# Sheet3.net
KiCad netlist of a schematic drawn in Altium Designer
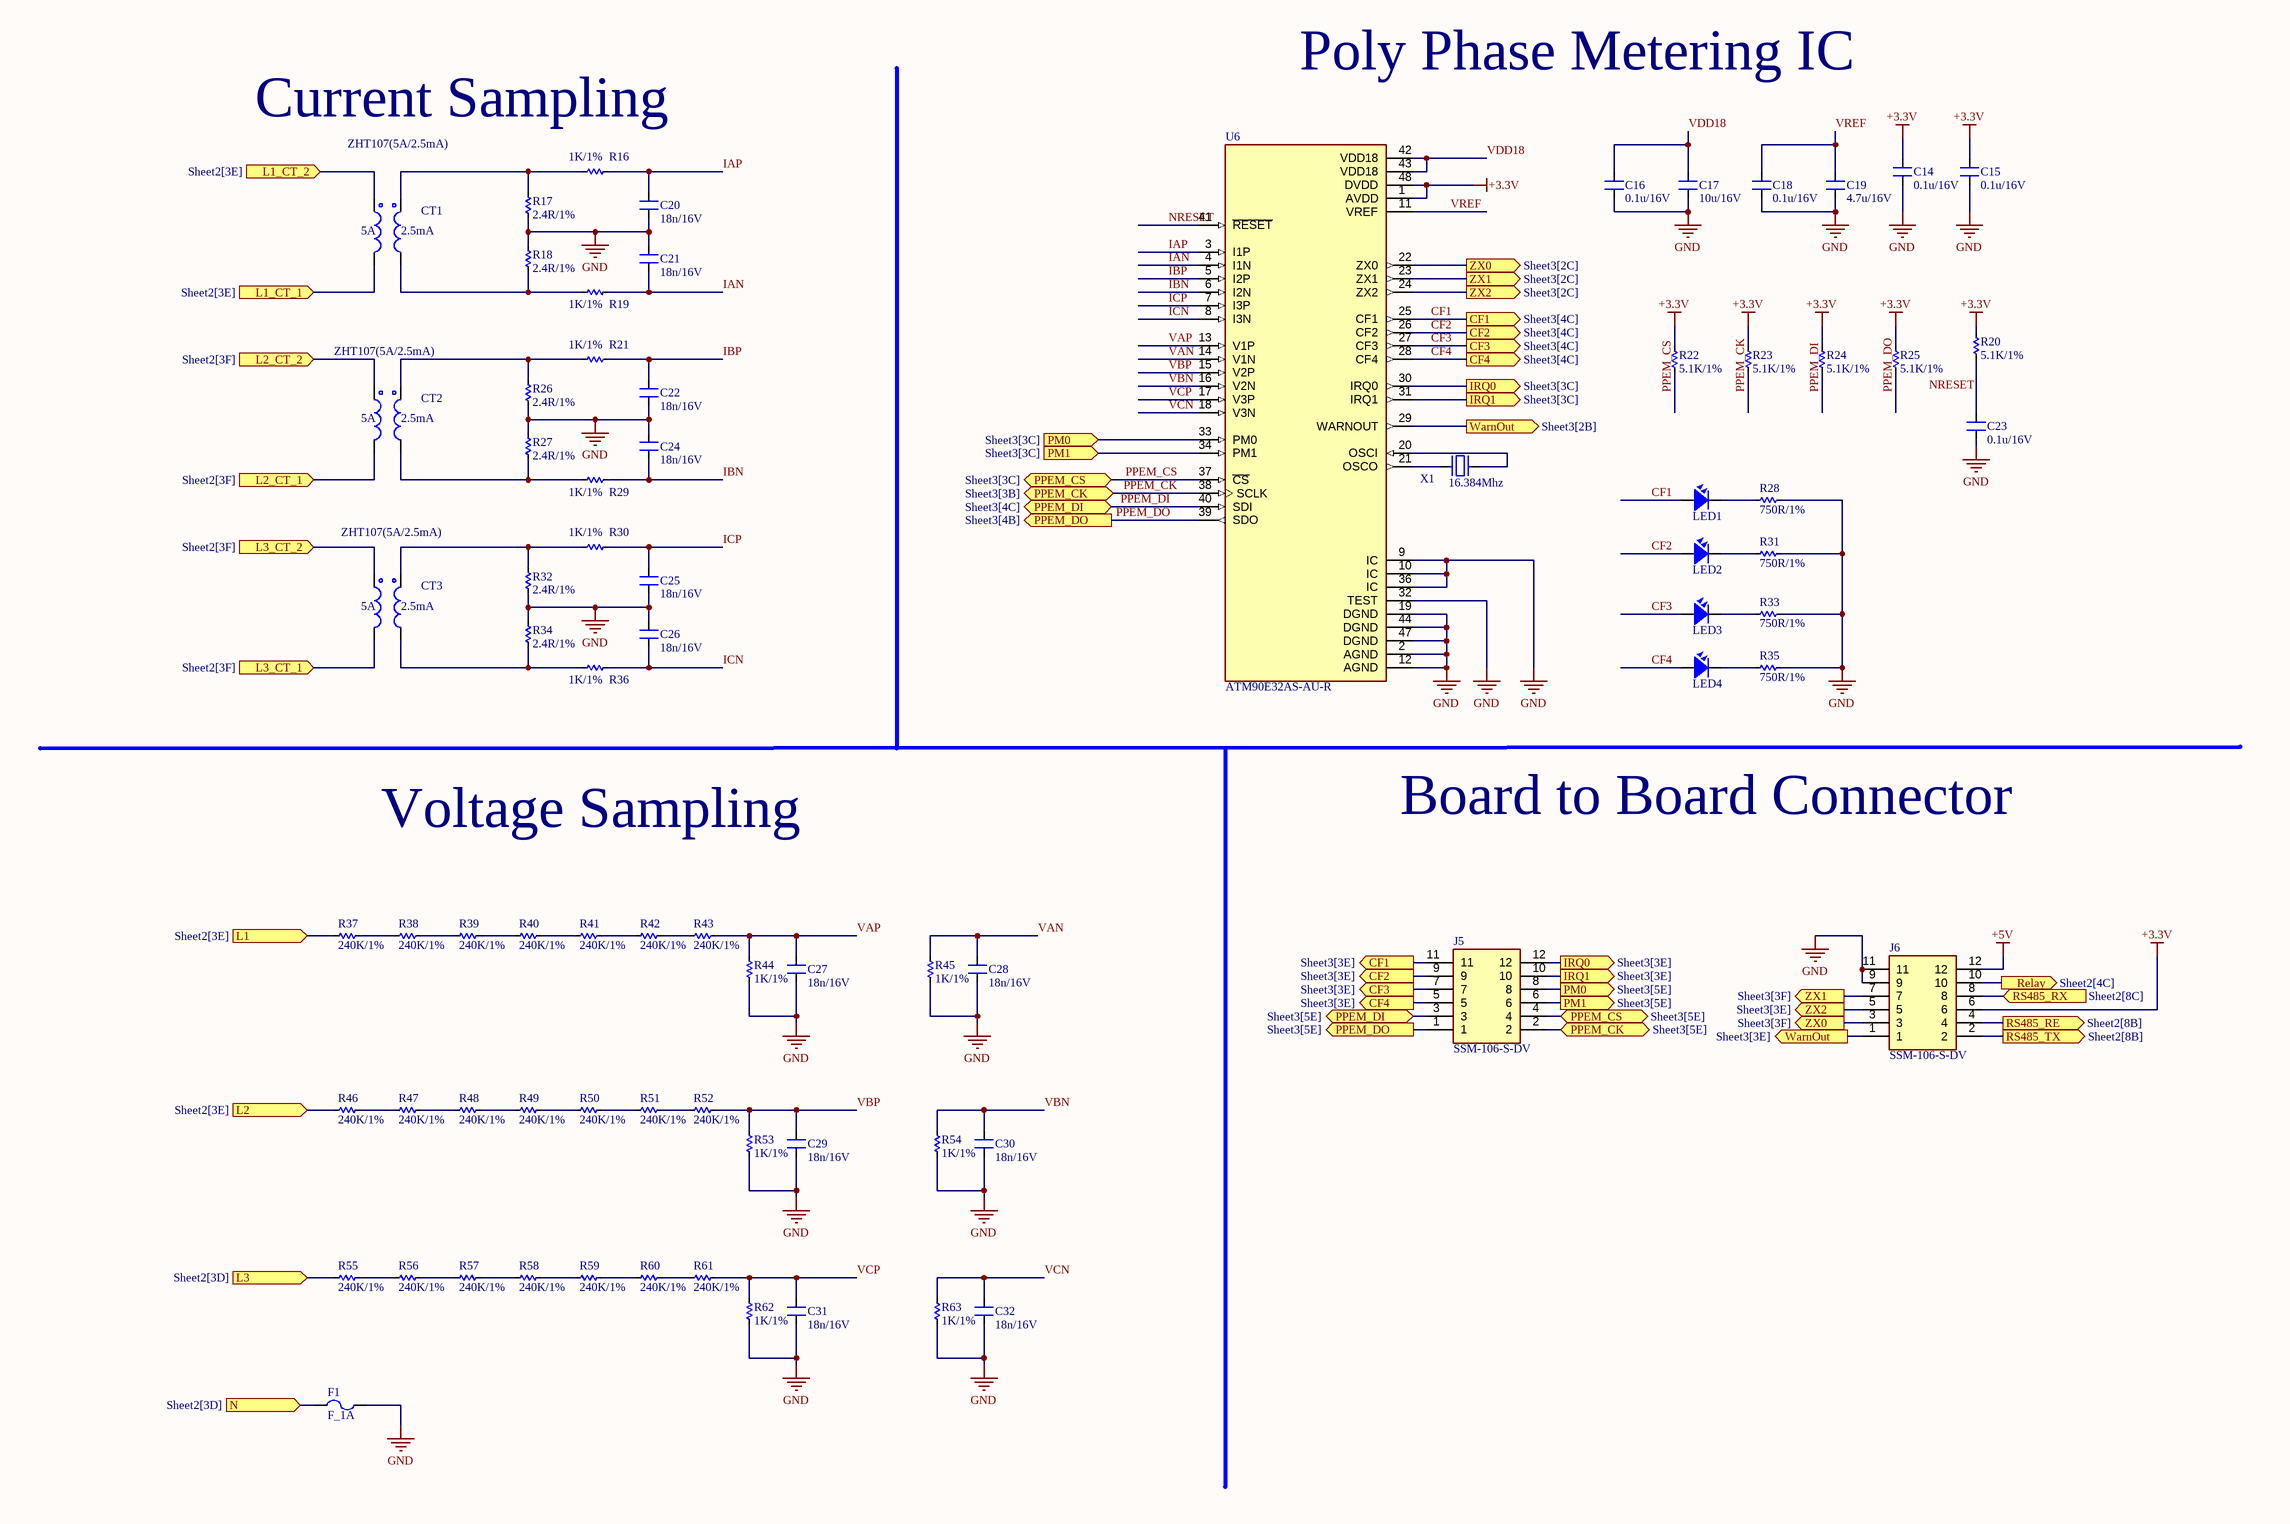
[diagram p0: Sheet3.SchDoc]

(export (version "E")
  (design (tool "Eeschema 10.0.6"))
  (components
    (comp (ref "C14")
      (value "0.1u/16V")
      (footprint "CAP_C_2012X110")
      (libsource (lib "DAK_Altium_Integrated_Lib") (part "CAP_SMD"))
    )
    (comp (ref "C15")
      (value "0.1u/16V")
      (footprint "CAP_C_2012X110")
      (libsource (lib "DAK_Altium_Integrated_Lib") (part "CAP_SMD"))
    )
    (comp (ref "C16")
      (value "0.1u/16V")
      (footprint "CAP_C_2012X110")
      (libsource (lib "DAK_Altium_Integrated_Lib") (part "CAP_SMD"))
    )
    (comp (ref "C17")
      (value "10u/16V")
      (footprint "CAP_C_2012X110")
      (libsource (lib "DAK_Altium_Integrated_Lib") (part "CAP_SMD"))
    )
    (comp (ref "C18")
      (value "0.1u/16V")
      (footprint "CAP_C_2012X110")
      (libsource (lib "DAK_Altium_Integrated_Lib") (part "CAP_SMD"))
    )
    (comp (ref "C19")
      (value "4.7u/16V")
      (footprint "CAP_C_2012X110")
      (libsource (lib "DAK_Altium_Integrated_Lib") (part "CAP_SMD"))
    )
    (comp (ref "C20")
      (value "18n/16V")
      (footprint "CAP_C_2012X110")
      (libsource (lib "DAK_Altium_Integrated_Lib") (part "CAP_SMD"))
    )
    (comp (ref "C21")
      (value "18n/16V")
      (footprint "CAP_C_2012X110")
      (libsource (lib "DAK_Altium_Integrated_Lib") (part "CAP_SMD"))
    )
    (comp (ref "C22")
      (value "18n/16V")
      (footprint "CAP_C_2012X110")
      (libsource (lib "DAK_Altium_Integrated_Lib") (part "CAP_SMD"))
    )
    (comp (ref "C23")
      (value "0.1u/16V")
      (footprint "CAP_C_2012X110")
      (libsource (lib "DAK_Altium_Integrated_Lib") (part "CAP_SMD"))
    )
    (comp (ref "C24")
      (value "18n/16V")
      (footprint "CAP_C_2012X110")
      (libsource (lib "DAK_Altium_Integrated_Lib") (part "CAP_SMD"))
    )
    (comp (ref "C25")
      (value "18n/16V")
      (footprint "CAP_C_2012X110")
      (libsource (lib "DAK_Altium_Integrated_Lib") (part "CAP_SMD"))
    )
    (comp (ref "C26")
      (value "18n/16V")
      (footprint "CAP_C_2012X110")
      (libsource (lib "DAK_Altium_Integrated_Lib") (part "CAP_SMD"))
    )
    (comp (ref "C27")
      (value "18n/16V")
      (footprint "CAP_C_2012X110")
      (libsource (lib "DAK_Altium_Integrated_Lib") (part "CAP_SMD"))
    )
    (comp (ref "C28")
      (value "18n/16V")
      (footprint "CAP_C_2012X110")
      (libsource (lib "DAK_Altium_Integrated_Lib") (part "CAP_SMD"))
    )
    (comp (ref "C29")
      (value "18n/16V")
      (footprint "CAP_C_2012X110")
      (libsource (lib "DAK_Altium_Integrated_Lib") (part "CAP_SMD"))
    )
    (comp (ref "C30")
      (value "18n/16V")
      (footprint "CAP_C_2012X110")
      (libsource (lib "DAK_Altium_Integrated_Lib") (part "CAP_SMD"))
    )
    (comp (ref "C31")
      (value "18n/16V")
      (footprint "CAP_C_2012X110")
      (libsource (lib "DAK_Altium_Integrated_Lib") (part "CAP_SMD"))
    )
    (comp (ref "C32")
      (value "18n/16V")
      (footprint "CAP_C_2012X110")
      (libsource (lib "DAK_Altium_Integrated_Lib") (part "CAP_SMD"))
    )
    (comp (ref "CT1")
      (value "ZHT107(5A/2.5mA)")
      (footprint "ZHT107")
      (description "C5183046")
      (libsource (lib "PowerMeter") (part "ZHT-107"))
    )
    (comp (ref "CT2")
      (value "ZHT107(5A/2.5mA)")
      (footprint "ZHT107")
      (description "C5183046")
      (libsource (lib "PowerMeter") (part "ZHT-107"))
    )
    (comp (ref "CT3")
      (value "ZHT107(5A/2.5mA)")
      (footprint "ZHT107")
      (description "C5183046")
      (libsource (lib "PowerMeter") (part "ZHT-107"))
    )
    (comp (ref "F1")
      (value "F_1A")
      (footprint "FUSC6127X294N")
      (description "Fuse")
      (fields (field (name "DESIGNED BY") "VanDungEvn"))
      (libsource (lib "PowerMeter") (part "Fuse"))
    )
    (comp (ref "J5")
      (value "SSM-106-S-DV")
      (footprint "SSM-106-XXX-DV-BE")
      (description "Connector")
      (fields
        (field (name "MANUFACTURER_PART_NUMBER") "SSM-105-S-DV")
        (field (name "MOUSER PART NUMBER") "200-SSM105SDV")
      )
      (libsource (lib "PowerMeter") (part "SSM-106-S-DV"))
    )
    (comp (ref "J6")
      (value "SSM-106-S-DV")
      (footprint "SSM-106-XXX-DV-BE")
      (description "Connector")
      (fields
        (field (name "MANUFACTURER_PART_NUMBER") "SSM-105-S-DV")
        (field (name "MOUSER PART NUMBER") "200-SSM105SDV")
      )
      (libsource (lib "PowerMeter") (part "SSM-106-S-DV"))
    )
    (comp (ref "LED1") (value "LED") (footprint "LED-0805-Blue") (libsource (lib "Library") (part "LED SMD")))
    (comp (ref "LED2") (value "LED") (footprint "LED-0805-Blue") (libsource (lib "Library") (part "LED SMD")))
    (comp (ref "LED3") (value "LED") (footprint "LED-0805-Blue") (libsource (lib "Library") (part "LED SMD")))
    (comp (ref "LED4") (value "LED") (footprint "LED-0805-Blue") (libsource (lib "Library") (part "LED SMD")))
    (comp (ref "R16")
      (value "1K/1%")
      (footprint "RES_C_2012X65")
      (description "Resistor")
      (fields
        (field (name "MANUFACTURER") "Generic Components")
        (field (name "PUBLISHER") "Altium Hobart Technology Centre")
      )
      (libsource (lib "Library") (part "Res-SMD"))
    )
    (comp (ref "R17")
      (value "2.4R/1%")
      (footprint "RES_C_2012X65")
      (description "Resistor")
      (fields
        (field (name "MANUFACTURER") "Generic Components")
        (field (name "PUBLISHER") "Altium Hobart Technology Centre")
      )
      (libsource (lib "Library") (part "Res-SMD"))
    )
    (comp (ref "R18")
      (value "2.4R/1%")
      (footprint "RES_C_2012X65")
      (description "Resistor")
      (fields
        (field (name "MANUFACTURER") "Generic Components")
        (field (name "PUBLISHER") "Altium Hobart Technology Centre")
      )
      (libsource (lib "Library") (part "Res-SMD"))
    )
    (comp (ref "R19")
      (value "1K/1%")
      (footprint "RES_C_2012X65")
      (description "Resistor")
      (fields
        (field (name "MANUFACTURER") "Generic Components")
        (field (name "PUBLISHER") "Altium Hobart Technology Centre")
      )
      (libsource (lib "Library") (part "Res-SMD"))
    )
    (comp (ref "R20")
      (value "5.1K/1%")
      (footprint "RES_C_2012X65")
      (description "Resistor")
      (fields
        (field (name "MANUFACTURER") "Generic Components")
        (field (name "PUBLISHER") "Altium Hobart Technology Centre")
      )
      (libsource (lib "Library") (part "Res-SMD"))
    )
    (comp (ref "R21")
      (value "1K/1%")
      (footprint "RES_C_2012X65")
      (description "Resistor")
      (fields
        (field (name "MANUFACTURER") "Generic Components")
        (field (name "PUBLISHER") "Altium Hobart Technology Centre")
      )
      (libsource (lib "Library") (part "Res-SMD"))
    )
    (comp (ref "R22")
      (value "5.1K/1%")
      (footprint "RES_C_2012X65")
      (description "Resistor")
      (fields
        (field (name "MANUFACTURER") "Generic Components")
        (field (name "PUBLISHER") "Altium Hobart Technology Centre")
      )
      (libsource (lib "Library") (part "Res-SMD"))
    )
    (comp (ref "R23")
      (value "5.1K/1%")
      (footprint "RES_C_2012X65")
      (description "Resistor")
      (fields
        (field (name "MANUFACTURER") "Generic Components")
        (field (name "PUBLISHER") "Altium Hobart Technology Centre")
      )
      (libsource (lib "Library") (part "Res-SMD"))
    )
    (comp (ref "R24")
      (value "5.1K/1%")
      (footprint "RES_C_2012X65")
      (description "Resistor")
      (fields
        (field (name "MANUFACTURER") "Generic Components")
        (field (name "PUBLISHER") "Altium Hobart Technology Centre")
      )
      (libsource (lib "Library") (part "Res-SMD"))
    )
    (comp (ref "R25")
      (value "5.1K/1%")
      (footprint "RES_C_2012X65")
      (description "Resistor")
      (fields
        (field (name "MANUFACTURER") "Generic Components")
        (field (name "PUBLISHER") "Altium Hobart Technology Centre")
      )
      (libsource (lib "Library") (part "Res-SMD"))
    )
    (comp (ref "R26")
      (value "2.4R/1%")
      (footprint "RES_C_2012X65")
      (description "Resistor")
      (fields
        (field (name "MANUFACTURER") "Generic Components")
        (field (name "PUBLISHER") "Altium Hobart Technology Centre")
      )
      (libsource (lib "Library") (part "Res-SMD"))
    )
    (comp (ref "R27")
      (value "2.4R/1%")
      (footprint "RES_C_2012X65")
      (description "Resistor")
      (fields
        (field (name "MANUFACTURER") "Generic Components")
        (field (name "PUBLISHER") "Altium Hobart Technology Centre")
      )
      (libsource (lib "Library") (part "Res-SMD"))
    )
    (comp (ref "R28")
      (value "750R/1%")
      (footprint "RES_C_2012X65")
      (description "Resistor")
      (fields
        (field (name "MANUFACTURER") "Generic Components")
        (field (name "PUBLISHER") "Altium Hobart Technology Centre")
      )
      (libsource (lib "Library") (part "Res-SMD"))
    )
    (comp (ref "R29")
      (value "1K/1%")
      (footprint "RES_C_2012X65")
      (description "Resistor")
      (fields
        (field (name "MANUFACTURER") "Generic Components")
        (field (name "PUBLISHER") "Altium Hobart Technology Centre")
      )
      (libsource (lib "Library") (part "Res-SMD"))
    )
    (comp (ref "R30")
      (value "1K/1%")
      (footprint "RES_C_2012X65")
      (description "Resistor")
      (fields
        (field (name "MANUFACTURER") "Generic Components")
        (field (name "PUBLISHER") "Altium Hobart Technology Centre")
      )
      (libsource (lib "Library") (part "Res-SMD"))
    )
    (comp (ref "R31")
      (value "750R/1%")
      (footprint "RES_C_2012X65")
      (description "Resistor")
      (fields
        (field (name "MANUFACTURER") "Generic Components")
        (field (name "PUBLISHER") "Altium Hobart Technology Centre")
      )
      (libsource (lib "Library") (part "Res-SMD"))
    )
    (comp (ref "R32")
      (value "2.4R/1%")
      (footprint "RES_C_2012X65")
      (description "Resistor")
      (fields
        (field (name "MANUFACTURER") "Generic Components")
        (field (name "PUBLISHER") "Altium Hobart Technology Centre")
      )
      (libsource (lib "Library") (part "Res-SMD"))
    )
    (comp (ref "R33")
      (value "750R/1%")
      (footprint "RES_C_2012X65")
      (description "Resistor")
      (fields
        (field (name "MANUFACTURER") "Generic Components")
        (field (name "PUBLISHER") "Altium Hobart Technology Centre")
      )
      (libsource (lib "Library") (part "Res-SMD"))
    )
    (comp (ref "R34")
      (value "2.4R/1%")
      (footprint "RES_C_2012X65")
      (description "Resistor")
      (fields
        (field (name "MANUFACTURER") "Generic Components")
        (field (name "PUBLISHER") "Altium Hobart Technology Centre")
      )
      (libsource (lib "Library") (part "Res-SMD"))
    )
    (comp (ref "R35")
      (value "750R/1%")
      (footprint "RES_C_2012X65")
      (description "Resistor")
      (fields
        (field (name "MANUFACTURER") "Generic Components")
        (field (name "PUBLISHER") "Altium Hobart Technology Centre")
      )
      (libsource (lib "Library") (part "Res-SMD"))
    )
    (comp (ref "R36")
      (value "1K/1%")
      (footprint "RES_C_2012X65")
      (description "Resistor")
      (fields
        (field (name "MANUFACTURER") "Generic Components")
        (field (name "PUBLISHER") "Altium Hobart Technology Centre")
      )
      (libsource (lib "Library") (part "Res-SMD"))
    )
    (comp (ref "R37")
      (value "240K/1%")
      (footprint "RES_C_2012X65")
      (description "Resistor")
      (fields
        (field (name "MANUFACTURER") "Generic Components")
        (field (name "PUBLISHER") "Altium Hobart Technology Centre")
      )
      (libsource (lib "Library") (part "Res-SMD"))
    )
    (comp (ref "R38")
      (value "240K/1%")
      (footprint "RES_C_2012X65")
      (description "Resistor")
      (fields
        (field (name "MANUFACTURER") "Generic Components")
        (field (name "PUBLISHER") "Altium Hobart Technology Centre")
      )
      (libsource (lib "Library") (part "Res-SMD"))
    )
    (comp (ref "R39")
      (value "240K/1%")
      (footprint "RES_C_2012X65")
      (description "Resistor")
      (fields
        (field (name "MANUFACTURER") "Generic Components")
        (field (name "PUBLISHER") "Altium Hobart Technology Centre")
      )
      (libsource (lib "Library") (part "Res-SMD"))
    )
    (comp (ref "R40")
      (value "240K/1%")
      (footprint "RES_C_2012X65")
      (description "Resistor")
      (fields
        (field (name "MANUFACTURER") "Generic Components")
        (field (name "PUBLISHER") "Altium Hobart Technology Centre")
      )
      (libsource (lib "Library") (part "Res-SMD"))
    )
    (comp (ref "R41")
      (value "240K/1%")
      (footprint "RES_C_2012X65")
      (description "Resistor")
      (fields
        (field (name "MANUFACTURER") "Generic Components")
        (field (name "PUBLISHER") "Altium Hobart Technology Centre")
      )
      (libsource (lib "Library") (part "Res-SMD"))
    )
    (comp (ref "R42")
      (value "240K/1%")
      (footprint "RES_C_2012X65")
      (description "Resistor")
      (fields
        (field (name "MANUFACTURER") "Generic Components")
        (field (name "PUBLISHER") "Altium Hobart Technology Centre")
      )
      (libsource (lib "Library") (part "Res-SMD"))
    )
    (comp (ref "R43")
      (value "240K/1%")
      (footprint "RES_C_2012X65")
      (description "Resistor")
      (fields
        (field (name "MANUFACTURER") "Generic Components")
        (field (name "PUBLISHER") "Altium Hobart Technology Centre")
      )
      (libsource (lib "Library") (part "Res-SMD"))
    )
    (comp (ref "R44")
      (value "1K/1%")
      (footprint "RES_C_2012X65")
      (description "Resistor")
      (fields
        (field (name "MANUFACTURER") "Generic Components")
        (field (name "PUBLISHER") "Altium Hobart Technology Centre")
      )
      (libsource (lib "Library") (part "Res-SMD"))
    )
    (comp (ref "R45")
      (value "1K/1%")
      (footprint "RES_C_2012X65")
      (description "Resistor")
      (fields
        (field (name "MANUFACTURER") "Generic Components")
        (field (name "PUBLISHER") "Altium Hobart Technology Centre")
      )
      (libsource (lib "Library") (part "Res-SMD"))
    )
    (comp (ref "R46")
      (value "240K/1%")
      (footprint "RES_C_2012X65")
      (description "Resistor")
      (fields
        (field (name "MANUFACTURER") "Generic Components")
        (field (name "PUBLISHER") "Altium Hobart Technology Centre")
      )
      (libsource (lib "Library") (part "Res-SMD"))
    )
    (comp (ref "R47")
      (value "240K/1%")
      (footprint "RES_C_2012X65")
      (description "Resistor")
      (fields
        (field (name "MANUFACTURER") "Generic Components")
        (field (name "PUBLISHER") "Altium Hobart Technology Centre")
      )
      (libsource (lib "Library") (part "Res-SMD"))
    )
    (comp (ref "R48")
      (value "240K/1%")
      (footprint "RES_C_2012X65")
      (description "Resistor")
      (fields
        (field (name "MANUFACTURER") "Generic Components")
        (field (name "PUBLISHER") "Altium Hobart Technology Centre")
      )
      (libsource (lib "Library") (part "Res-SMD"))
    )
    (comp (ref "R49")
      (value "240K/1%")
      (footprint "RES_C_2012X65")
      (description "Resistor")
      (fields
        (field (name "MANUFACTURER") "Generic Components")
        (field (name "PUBLISHER") "Altium Hobart Technology Centre")
      )
      (libsource (lib "Library") (part "Res-SMD"))
    )
    (comp (ref "R50")
      (value "240K/1%")
      (footprint "RES_C_2012X65")
      (description "Resistor")
      (fields
        (field (name "MANUFACTURER") "Generic Components")
        (field (name "PUBLISHER") "Altium Hobart Technology Centre")
      )
      (libsource (lib "Library") (part "Res-SMD"))
    )
    (comp (ref "R51")
      (value "240K/1%")
      (footprint "RES_C_2012X65")
      (description "Resistor")
      (fields
        (field (name "MANUFACTURER") "Generic Components")
        (field (name "PUBLISHER") "Altium Hobart Technology Centre")
      )
      (libsource (lib "Library") (part "Res-SMD"))
    )
    (comp (ref "R52")
      (value "240K/1%")
      (footprint "RES_C_2012X65")
      (description "Resistor")
      (fields
        (field (name "MANUFACTURER") "Generic Components")
        (field (name "PUBLISHER") "Altium Hobart Technology Centre")
      )
      (libsource (lib "Library") (part "Res-SMD"))
    )
    (comp (ref "R53")
      (value "1K/1%")
      (footprint "RES_C_2012X65")
      (description "Resistor")
      (fields
        (field (name "MANUFACTURER") "Generic Components")
        (field (name "PUBLISHER") "Altium Hobart Technology Centre")
      )
      (libsource (lib "Library") (part "Res-SMD"))
    )
    (comp (ref "R54")
      (value "1K/1%")
      (footprint "RES_C_2012X65")
      (description "Resistor")
      (fields
        (field (name "MANUFACTURER") "Generic Components")
        (field (name "PUBLISHER") "Altium Hobart Technology Centre")
      )
      (libsource (lib "Library") (part "Res-SMD"))
    )
    (comp (ref "R55")
      (value "240K/1%")
      (footprint "RES_C_2012X65")
      (description "Resistor")
      (fields
        (field (name "MANUFACTURER") "Generic Components")
        (field (name "PUBLISHER") "Altium Hobart Technology Centre")
      )
      (libsource (lib "Library") (part "Res-SMD"))
    )
    (comp (ref "R56")
      (value "240K/1%")
      (footprint "RES_C_2012X65")
      (description "Resistor")
      (fields
        (field (name "MANUFACTURER") "Generic Components")
        (field (name "PUBLISHER") "Altium Hobart Technology Centre")
      )
      (libsource (lib "Library") (part "Res-SMD"))
    )
    (comp (ref "R57")
      (value "240K/1%")
      (footprint "RES_C_2012X65")
      (description "Resistor")
      (fields
        (field (name "MANUFACTURER") "Generic Components")
        (field (name "PUBLISHER") "Altium Hobart Technology Centre")
      )
      (libsource (lib "Library") (part "Res-SMD"))
    )
    (comp (ref "R58")
      (value "240K/1%")
      (footprint "RES_C_2012X65")
      (description "Resistor")
      (fields
        (field (name "MANUFACTURER") "Generic Components")
        (field (name "PUBLISHER") "Altium Hobart Technology Centre")
      )
      (libsource (lib "Library") (part "Res-SMD"))
    )
    (comp (ref "R59")
      (value "240K/1%")
      (footprint "RES_C_2012X65")
      (description "Resistor")
      (fields
        (field (name "MANUFACTURER") "Generic Components")
        (field (name "PUBLISHER") "Altium Hobart Technology Centre")
      )
      (libsource (lib "Library") (part "Res-SMD"))
    )
    (comp (ref "R60")
      (value "240K/1%")
      (footprint "RES_C_2012X65")
      (description "Resistor")
      (fields
        (field (name "MANUFACTURER") "Generic Components")
        (field (name "PUBLISHER") "Altium Hobart Technology Centre")
      )
      (libsource (lib "Library") (part "Res-SMD"))
    )
    (comp (ref "R61")
      (value "240K/1%")
      (footprint "RES_C_2012X65")
      (description "Resistor")
      (fields
        (field (name "MANUFACTURER") "Generic Components")
        (field (name "PUBLISHER") "Altium Hobart Technology Centre")
      )
      (libsource (lib "Library") (part "Res-SMD"))
    )
    (comp (ref "R62")
      (value "1K/1%")
      (footprint "RES_C_2012X65")
      (description "Resistor")
      (fields
        (field (name "MANUFACTURER") "Generic Components")
        (field (name "PUBLISHER") "Altium Hobart Technology Centre")
      )
      (libsource (lib "Library") (part "Res-SMD"))
    )
    (comp (ref "R63")
      (value "1K/1%")
      (footprint "RES_C_2012X65")
      (description "Resistor")
      (fields
        (field (name "MANUFACTURER") "Generic Components")
        (field (name "PUBLISHER") "Altium Hobart Technology Centre")
      )
      (libsource (lib "Library") (part "Res-SMD"))
    )
    (comp (ref "U6")
      (value "ATM90E32AS-AU-R")
      (footprint "TSQFP50P900X900X120-48N")
      (description "IC ENERGY METER 1.8V/3V 48TQFP")
      (fields (field (name "MF") "Microchip"))
      (libsource (lib "PowerMeter") (part "ATM90E32AS-AU-R"))
    )
    (comp (ref "X1")
      (value "16.384Mhz")
      (footprint "XT2-SMD")
      (description "Crystal, 32.768 KHz, -40 to 85 degC, 3.2 x 1.5 x 0.9 mm SMD")
      (libsource (lib "Library") (part "XT2"))
    )
  )
  (nets
    (net (code "1") (name "+3.3V") (class "Default")
      (node (ref "C14") (pin "2") (pinfunction "2_2") (pintype "passive"))
      (node (ref "C15") (pin "2") (pinfunction "2_2") (pintype "passive"))
      (node (ref "J6") (pin "6") (pinfunction "6_6") (pintype "passive"))
      (node (ref "R20") (pin "2") (pinfunction "2_2") (pintype "passive"))
      (node (ref "R22") (pin "2") (pinfunction "2_2") (pintype "passive"))
      (node (ref "R23") (pin "2") (pinfunction "2_2") (pintype "passive"))
      (node (ref "R24") (pin "2") (pinfunction "2_2") (pintype "passive"))
      (node (ref "R25") (pin "2") (pinfunction "2_2") (pintype "passive"))
      (node (ref "U6") (pin "1") (pinfunction "AVDD_1") (pintype "power_in"))
      (node (ref "U6") (pin "48") (pinfunction "DVDD_48") (pintype "power_in"))
    )
    (net (code "2") (name "+5V") (class "Default")
      (node (ref "J6") (pin "12") (pinfunction "12_12") (pintype "passive"))
    )
    (net (code "3") (name "/CF1") (class "Default")
      (node (ref "J5") (pin "11") (pinfunction "11_11") (pintype "passive"))
      (node (ref "LED1") (pin "1") (pinfunction "1_1") (pintype "passive"))
      (node (ref "U6") (pin "25") (pinfunction "CF1_25") (pintype "output"))
    )
    (net (code "4") (name "/CF2") (class "Default")
      (node (ref "J5") (pin "9") (pinfunction "9_9") (pintype "passive"))
      (node (ref "LED2") (pin "1") (pinfunction "1_1") (pintype "passive"))
      (node (ref "U6") (pin "26") (pinfunction "CF2_26") (pintype "output"))
    )
    (net (code "5") (name "/CF3") (class "Default")
      (node (ref "J5") (pin "7") (pinfunction "7_7") (pintype "passive"))
      (node (ref "LED3") (pin "1") (pinfunction "1_1") (pintype "passive"))
      (node (ref "U6") (pin "27") (pinfunction "CF3_27") (pintype "output"))
    )
    (net (code "6") (name "/CF4") (class "Default")
      (node (ref "J5") (pin "5") (pinfunction "5_5") (pintype "passive"))
      (node (ref "LED4") (pin "1") (pinfunction "1_1") (pintype "passive"))
      (node (ref "U6") (pin "28") (pinfunction "CF4_28") (pintype "output"))
    )
    (net (code "7") (name "/IAN") (class "Default")
      (node (ref "C21") (pin "1") (pinfunction "1_1") (pintype "passive"))
      (node (ref "R19") (pin "2") (pinfunction "2_2") (pintype "passive"))
      (node (ref "U6") (pin "4") (pinfunction "I1N_4") (pintype "input"))
    )
    (net (code "8") (name "/IAP") (class "Default")
      (node (ref "C20") (pin "2") (pinfunction "2_2") (pintype "passive"))
      (node (ref "R16") (pin "2") (pinfunction "2_2") (pintype "passive"))
      (node (ref "U6") (pin "3") (pinfunction "I1P_3") (pintype "input"))
    )
    (net (code "9") (name "/IBN") (class "Default")
      (node (ref "C24") (pin "1") (pinfunction "1_1") (pintype "passive"))
      (node (ref "R29") (pin "2") (pinfunction "2_2") (pintype "passive"))
      (node (ref "U6") (pin "6") (pinfunction "I2N_6") (pintype "input"))
    )
    (net (code "10") (name "/IBP") (class "Default")
      (node (ref "C22") (pin "2") (pinfunction "2_2") (pintype "passive"))
      (node (ref "R21") (pin "2") (pinfunction "2_2") (pintype "passive"))
      (node (ref "U6") (pin "5") (pinfunction "I2P_5") (pintype "input"))
    )
    (net (code "11") (name "/ICN") (class "Default")
      (node (ref "C26") (pin "1") (pinfunction "1_1") (pintype "passive"))
      (node (ref "R36") (pin "2") (pinfunction "2_2") (pintype "passive"))
      (node (ref "U6") (pin "8") (pinfunction "I3N_8") (pintype "input"))
    )
    (net (code "12") (name "/ICP") (class "Default")
      (node (ref "C25") (pin "2") (pinfunction "2_2") (pintype "passive"))
      (node (ref "R30") (pin "2") (pinfunction "2_2") (pintype "passive"))
      (node (ref "U6") (pin "7") (pinfunction "I3P_7") (pintype "input"))
    )
    (net (code "13") (name "/IRQ0") (class "Default")
      (node (ref "J5") (pin "12") (pinfunction "12_12") (pintype "passive"))
      (node (ref "U6") (pin "30") (pinfunction "IRQ0_30") (pintype "output"))
    )
    (net (code "14") (name "/IRQ1") (class "Default")
      (node (ref "J5") (pin "10") (pinfunction "10_10") (pintype "passive"))
      (node (ref "U6") (pin "31") (pinfunction "IRQ1_31") (pintype "output"))
    )
    (net (code "15") (name "/L1") (class "Default")
      (node (ref "R37") (pin "2") (pinfunction "2_2") (pintype "passive"))
    )
    (net (code "16") (name "/L1_CT_1") (class "Default")
      (node (ref "CT1") (pin "2") (pinfunction "2_2") (pintype "passive"))
    )
    (net (code "17") (name "/L1_CT_2") (class "Default")
      (node (ref "CT1") (pin "1") (pinfunction "1_1") (pintype "passive"))
    )
    (net (code "18") (name "/L2") (class "Default")
      (node (ref "R46") (pin "2") (pinfunction "2_2") (pintype "passive"))
    )
    (net (code "19") (name "/L2_CT_1") (class "Default")
      (node (ref "CT2") (pin "2") (pinfunction "2_2") (pintype "passive"))
    )
    (net (code "20") (name "/L2_CT_2") (class "Default")
      (node (ref "CT2") (pin "1") (pinfunction "1_1") (pintype "passive"))
    )
    (net (code "21") (name "/L3") (class "Default")
      (node (ref "R55") (pin "2") (pinfunction "2_2") (pintype "passive"))
    )
    (net (code "22") (name "/L3_CT_1") (class "Default")
      (node (ref "CT3") (pin "2") (pinfunction "2_2") (pintype "passive"))
    )
    (net (code "23") (name "/L3_CT_2") (class "Default")
      (node (ref "CT3") (pin "1") (pinfunction "1_1") (pintype "passive"))
    )
    (net (code "24") (name "/N") (class "Default")
      (node (ref "F1") (pin "1") (pinfunction "1_1") (pintype "passive"))
    )
    (net (code "25") (name "/NRESET") (class "Default")
      (node (ref "C23") (pin "2") (pinfunction "2_2") (pintype "passive"))
      (node (ref "R20") (pin "1") (pinfunction "1_1") (pintype "passive"))
      (node (ref "U6") (pin "41") (pinfunction "~{RESET}_41") (pintype "input"))
    )
    (net (code "26") (name "/PM0") (class "Default")
      (node (ref "J5") (pin "8") (pinfunction "8_8") (pintype "passive"))
      (node (ref "U6") (pin "33") (pinfunction "PM0_33") (pintype "input"))
    )
    (net (code "27") (name "/PM1") (class "Default")
      (node (ref "J5") (pin "6") (pinfunction "6_6") (pintype "passive"))
      (node (ref "U6") (pin "34") (pinfunction "PM1_34") (pintype "input"))
    )
    (net (code "28") (name "/PPEM_CK") (class "Default")
      (node (ref "J5") (pin "2") (pinfunction "2_2") (pintype "passive"))
      (node (ref "R23") (pin "1") (pinfunction "1_1") (pintype "passive"))
      (node (ref "U6") (pin "38") (pinfunction "SCLK_38") (pintype "input"))
    )
    (net (code "29") (name "/PPEM_CS") (class "Default")
      (node (ref "J5") (pin "4") (pinfunction "4_4") (pintype "passive"))
      (node (ref "R22") (pin "1") (pinfunction "1_1") (pintype "passive"))
      (node (ref "U6") (pin "37") (pinfunction "~{CS}_37") (pintype "input"))
    )
    (net (code "30") (name "/PPEM_DI") (class "Default")
      (node (ref "J5") (pin "3") (pinfunction "3_3") (pintype "passive"))
      (node (ref "R24") (pin "1") (pinfunction "1_1") (pintype "passive"))
      (node (ref "U6") (pin "40") (pinfunction "SDI_40") (pintype "input"))
    )
    (net (code "31") (name "/PPEM_DO") (class "Default")
      (node (ref "J5") (pin "1") (pinfunction "1_1") (pintype "passive"))
      (node (ref "R25") (pin "1") (pinfunction "1_1") (pintype "passive"))
      (node (ref "U6") (pin "39") (pinfunction "SDO_39") (pintype "output"))
    )
    (net (code "32") (name "/RS485_RE") (class "Default")
      (node (ref "J6") (pin "4") (pinfunction "4_4") (pintype "passive"))
    )
    (net (code "33") (name "/RS485_RX") (class "Default")
      (node (ref "J6") (pin "8") (pinfunction "8_8") (pintype "passive"))
    )
    (net (code "34") (name "/RS485_TX") (class "Default")
      (node (ref "J6") (pin "2") (pinfunction "2_2") (pintype "passive"))
    )
    (net (code "35") (name "/Relay") (class "Default")
      (node (ref "J6") (pin "10") (pinfunction "10_10") (pintype "passive"))
    )
    (net (code "36") (name "/VAN") (class "Default")
      (node (ref "C28") (pin "2") (pinfunction "2_2") (pintype "passive"))
      (node (ref "R45") (pin "1") (pinfunction "1_1") (pintype "passive"))
      (node (ref "U6") (pin "14") (pinfunction "V1N_14") (pintype "input"))
    )
    (net (code "37") (name "/VAP") (class "Default")
      (node (ref "C27") (pin "2") (pinfunction "2_2") (pintype "passive"))
      (node (ref "R43") (pin "1") (pinfunction "1_1") (pintype "passive"))
      (node (ref "R44") (pin "1") (pinfunction "1_1") (pintype "passive"))
      (node (ref "U6") (pin "13") (pinfunction "V1P_13") (pintype "input"))
    )
    (net (code "38") (name "/VBN") (class "Default")
      (node (ref "C30") (pin "2") (pinfunction "2_2") (pintype "passive"))
      (node (ref "R54") (pin "1") (pinfunction "1_1") (pintype "passive"))
      (node (ref "U6") (pin "16") (pinfunction "V2N_16") (pintype "input"))
    )
    (net (code "39") (name "/VBP") (class "Default")
      (node (ref "C29") (pin "2") (pinfunction "2_2") (pintype "passive"))
      (node (ref "R52") (pin "1") (pinfunction "1_1") (pintype "passive"))
      (node (ref "R53") (pin "1") (pinfunction "1_1") (pintype "passive"))
      (node (ref "U6") (pin "15") (pinfunction "V2P_15") (pintype "input"))
    )
    (net (code "40") (name "/VCN") (class "Default")
      (node (ref "C32") (pin "2") (pinfunction "2_2") (pintype "passive"))
      (node (ref "R63") (pin "1") (pinfunction "1_1") (pintype "passive"))
      (node (ref "U6") (pin "18") (pinfunction "V3N_18") (pintype "input"))
    )
    (net (code "41") (name "/VCP") (class "Default")
      (node (ref "C31") (pin "2") (pinfunction "2_2") (pintype "passive"))
      (node (ref "R61") (pin "1") (pinfunction "1_1") (pintype "passive"))
      (node (ref "R62") (pin "1") (pinfunction "1_1") (pintype "passive"))
      (node (ref "U6") (pin "17") (pinfunction "V3P_17") (pintype "input"))
    )
    (net (code "42") (name "/VDD18") (class "Default")
      (node (ref "C16") (pin "2") (pinfunction "2_2") (pintype "passive"))
      (node (ref "C17") (pin "2") (pinfunction "2_2") (pintype "passive"))
      (node (ref "U6") (pin "42") (pinfunction "VDD18_42") (pintype "power_in"))
      (node (ref "U6") (pin "43") (pinfunction "VDD18_43") (pintype "power_in"))
    )
    (net (code "43") (name "/VREF") (class "Default")
      (node (ref "C18") (pin "2") (pinfunction "2_2") (pintype "passive"))
      (node (ref "C19") (pin "2") (pinfunction "2_2") (pintype "passive"))
      (node (ref "U6") (pin "11") (pinfunction "VREF_11") (pintype "power_in"))
    )
    (net (code "44") (name "/WarnOut") (class "Default")
      (node (ref "J6") (pin "1") (pinfunction "1_1") (pintype "passive"))
      (node (ref "U6") (pin "29") (pinfunction "WARNOUT_29") (pintype "output"))
    )
    (net (code "45") (name "/ZX0") (class "Default")
      (node (ref "J6") (pin "3") (pinfunction "3_3") (pintype "passive"))
      (node (ref "U6") (pin "22") (pinfunction "ZX0_22") (pintype "output"))
    )
    (net (code "46") (name "/ZX1") (class "Default")
      (node (ref "J6") (pin "7") (pinfunction "7_7") (pintype "passive"))
      (node (ref "U6") (pin "23") (pinfunction "ZX1_23") (pintype "output"))
    )
    (net (code "47") (name "/ZX2") (class "Default")
      (node (ref "J6") (pin "5") (pinfunction "5_5") (pintype "passive"))
      (node (ref "U6") (pin "24") (pinfunction "ZX2_24") (pintype "output"))
    )
    (net (code "48") (name "GND") (class "Default")
      (node (ref "C14") (pin "1") (pinfunction "1_1") (pintype "passive"))
      (node (ref "C15") (pin "1") (pinfunction "1_1") (pintype "passive"))
      (node (ref "C16") (pin "1") (pinfunction "1_1") (pintype "passive"))
      (node (ref "C17") (pin "1") (pinfunction "1_1") (pintype "passive"))
      (node (ref "C18") (pin "1") (pinfunction "1_1") (pintype "passive"))
      (node (ref "C19") (pin "1") (pinfunction "1_1") (pintype "passive"))
      (node (ref "C20") (pin "1") (pinfunction "1_1") (pintype "passive"))
      (node (ref "C21") (pin "2") (pinfunction "2_2") (pintype "passive"))
      (node (ref "C22") (pin "1") (pinfunction "1_1") (pintype "passive"))
      (node (ref "C23") (pin "1") (pinfunction "1_1") (pintype "passive"))
      (node (ref "C24") (pin "2") (pinfunction "2_2") (pintype "passive"))
      (node (ref "C25") (pin "1") (pinfunction "1_1") (pintype "passive"))
      (node (ref "C26") (pin "2") (pinfunction "2_2") (pintype "passive"))
      (node (ref "C27") (pin "1") (pinfunction "1_1") (pintype "passive"))
      (node (ref "C28") (pin "1") (pinfunction "1_1") (pintype "passive"))
      (node (ref "C29") (pin "1") (pinfunction "1_1") (pintype "passive"))
      (node (ref "C30") (pin "1") (pinfunction "1_1") (pintype "passive"))
      (node (ref "C31") (pin "1") (pinfunction "1_1") (pintype "passive"))
      (node (ref "C32") (pin "1") (pinfunction "1_1") (pintype "passive"))
      (node (ref "F1") (pin "2") (pinfunction "2_2") (pintype "passive"))
      (node (ref "J6") (pin "11") (pinfunction "11_11") (pintype "passive"))
      (node (ref "J6") (pin "9") (pinfunction "9_9") (pintype "passive"))
      (node (ref "R17") (pin "2") (pinfunction "2_2") (pintype "passive"))
      (node (ref "R18") (pin "1") (pinfunction "1_1") (pintype "passive"))
      (node (ref "R26") (pin "2") (pinfunction "2_2") (pintype "passive"))
      (node (ref "R27") (pin "1") (pinfunction "1_1") (pintype "passive"))
      (node (ref "R28") (pin "2") (pinfunction "2_2") (pintype "passive"))
      (node (ref "R31") (pin "2") (pinfunction "2_2") (pintype "passive"))
      (node (ref "R32") (pin "2") (pinfunction "2_2") (pintype "passive"))
      (node (ref "R33") (pin "2") (pinfunction "2_2") (pintype "passive"))
      (node (ref "R34") (pin "1") (pinfunction "1_1") (pintype "passive"))
      (node (ref "R35") (pin "2") (pinfunction "2_2") (pintype "passive"))
      (node (ref "R44") (pin "2") (pinfunction "2_2") (pintype "passive"))
      (node (ref "R45") (pin "2") (pinfunction "2_2") (pintype "passive"))
      (node (ref "R53") (pin "2") (pinfunction "2_2") (pintype "passive"))
      (node (ref "R54") (pin "2") (pinfunction "2_2") (pintype "passive"))
      (node (ref "R62") (pin "2") (pinfunction "2_2") (pintype "passive"))
      (node (ref "R63") (pin "2") (pinfunction "2_2") (pintype "passive"))
      (node (ref "U6") (pin "10") (pinfunction "IC_10") (pintype "passive"))
      (node (ref "U6") (pin "12") (pinfunction "AGND_12") (pintype "power_in"))
      (node (ref "U6") (pin "19") (pinfunction "DGND_19") (pintype "power_in"))
      (node (ref "U6") (pin "2") (pinfunction "AGND_2") (pintype "power_in"))
      (node (ref "U6") (pin "32") (pinfunction "TEST_32") (pintype "passive"))
      (node (ref "U6") (pin "36") (pinfunction "IC_36") (pintype "passive"))
      (node (ref "U6") (pin "44") (pinfunction "DGND_44") (pintype "power_in"))
      (node (ref "U6") (pin "47") (pinfunction "DGND_47") (pintype "power_in"))
      (node (ref "U6") (pin "9") (pinfunction "IC_9") (pintype "passive"))
    )
    (net (code "49") (name "Net-(CT1-Pad3)") (class "Default")
      (node (ref "CT1") (pin "3") (pinfunction "3_3") (pintype "passive"))
      (node (ref "R16") (pin "1") (pinfunction "1_1") (pintype "passive"))
      (node (ref "R17") (pin "1") (pinfunction "1_1") (pintype "passive"))
    )
    (net (code "50") (name "Net-(CT1-Pad4)") (class "Default")
      (node (ref "CT1") (pin "4") (pinfunction "4_4") (pintype "passive"))
      (node (ref "R18") (pin "2") (pinfunction "2_2") (pintype "passive"))
      (node (ref "R19") (pin "1") (pinfunction "1_1") (pintype "passive"))
    )
    (net (code "51") (name "Net-(CT2-Pad3)") (class "Default")
      (node (ref "CT2") (pin "3") (pinfunction "3_3") (pintype "passive"))
      (node (ref "R21") (pin "1") (pinfunction "1_1") (pintype "passive"))
      (node (ref "R26") (pin "1") (pinfunction "1_1") (pintype "passive"))
    )
    (net (code "52") (name "Net-(CT2-Pad4)") (class "Default")
      (node (ref "CT2") (pin "4") (pinfunction "4_4") (pintype "passive"))
      (node (ref "R27") (pin "2") (pinfunction "2_2") (pintype "passive"))
      (node (ref "R29") (pin "1") (pinfunction "1_1") (pintype "passive"))
    )
    (net (code "53") (name "Net-(CT3-Pad3)") (class "Default")
      (node (ref "CT3") (pin "3") (pinfunction "3_3") (pintype "passive"))
      (node (ref "R30") (pin "1") (pinfunction "1_1") (pintype "passive"))
      (node (ref "R32") (pin "1") (pinfunction "1_1") (pintype "passive"))
    )
    (net (code "54") (name "Net-(CT3-Pad4)") (class "Default")
      (node (ref "CT3") (pin "4") (pinfunction "4_4") (pintype "passive"))
      (node (ref "R34") (pin "2") (pinfunction "2_2") (pintype "passive"))
      (node (ref "R36") (pin "1") (pinfunction "1_1") (pintype "passive"))
    )
    (net (code "55") (name "Net-(LED1-Pad2)") (class "Default")
      (node (ref "LED1") (pin "2") (pinfunction "2_2") (pintype "passive"))
      (node (ref "R28") (pin "1") (pinfunction "1_1") (pintype "passive"))
    )
    (net (code "56") (name "Net-(LED2-Pad2)") (class "Default")
      (node (ref "LED2") (pin "2") (pinfunction "2_2") (pintype "passive"))
      (node (ref "R31") (pin "1") (pinfunction "1_1") (pintype "passive"))
    )
    (net (code "57") (name "Net-(LED3-Pad2)") (class "Default")
      (node (ref "LED3") (pin "2") (pinfunction "2_2") (pintype "passive"))
      (node (ref "R33") (pin "1") (pinfunction "1_1") (pintype "passive"))
    )
    (net (code "58") (name "Net-(LED4-Pad2)") (class "Default")
      (node (ref "LED4") (pin "2") (pinfunction "2_2") (pintype "passive"))
      (node (ref "R35") (pin "1") (pinfunction "1_1") (pintype "passive"))
    )
    (net (code "59") (name "Net-(R37-Pad1)") (class "Default")
      (node (ref "R37") (pin "1") (pinfunction "1_1") (pintype "passive"))
      (node (ref "R38") (pin "2") (pinfunction "2_2") (pintype "passive"))
    )
    (net (code "60") (name "Net-(R38-Pad1)") (class "Default")
      (node (ref "R38") (pin "1") (pinfunction "1_1") (pintype "passive"))
      (node (ref "R39") (pin "2") (pinfunction "2_2") (pintype "passive"))
    )
    (net (code "61") (name "Net-(R39-Pad1)") (class "Default")
      (node (ref "R39") (pin "1") (pinfunction "1_1") (pintype "passive"))
      (node (ref "R40") (pin "2") (pinfunction "2_2") (pintype "passive"))
    )
    (net (code "62") (name "Net-(R40-Pad1)") (class "Default")
      (node (ref "R40") (pin "1") (pinfunction "1_1") (pintype "passive"))
      (node (ref "R41") (pin "2") (pinfunction "2_2") (pintype "passive"))
    )
    (net (code "63") (name "Net-(R41-Pad1)") (class "Default")
      (node (ref "R41") (pin "1") (pinfunction "1_1") (pintype "passive"))
      (node (ref "R42") (pin "2") (pinfunction "2_2") (pintype "passive"))
    )
    (net (code "64") (name "Net-(R42-Pad1)") (class "Default")
      (node (ref "R42") (pin "1") (pinfunction "1_1") (pintype "passive"))
      (node (ref "R43") (pin "2") (pinfunction "2_2") (pintype "passive"))
    )
    (net (code "65") (name "Net-(R46-Pad1)") (class "Default")
      (node (ref "R46") (pin "1") (pinfunction "1_1") (pintype "passive"))
      (node (ref "R47") (pin "2") (pinfunction "2_2") (pintype "passive"))
    )
    (net (code "66") (name "Net-(R47-Pad1)") (class "Default")
      (node (ref "R47") (pin "1") (pinfunction "1_1") (pintype "passive"))
      (node (ref "R48") (pin "2") (pinfunction "2_2") (pintype "passive"))
    )
    (net (code "67") (name "Net-(R48-Pad1)") (class "Default")
      (node (ref "R48") (pin "1") (pinfunction "1_1") (pintype "passive"))
      (node (ref "R49") (pin "2") (pinfunction "2_2") (pintype "passive"))
    )
    (net (code "68") (name "Net-(R49-Pad1)") (class "Default")
      (node (ref "R49") (pin "1") (pinfunction "1_1") (pintype "passive"))
      (node (ref "R50") (pin "2") (pinfunction "2_2") (pintype "passive"))
    )
    (net (code "69") (name "Net-(R50-Pad1)") (class "Default")
      (node (ref "R50") (pin "1") (pinfunction "1_1") (pintype "passive"))
      (node (ref "R51") (pin "2") (pinfunction "2_2") (pintype "passive"))
    )
    (net (code "70") (name "Net-(R51-Pad1)") (class "Default")
      (node (ref "R51") (pin "1") (pinfunction "1_1") (pintype "passive"))
      (node (ref "R52") (pin "2") (pinfunction "2_2") (pintype "passive"))
    )
    (net (code "71") (name "Net-(R55-Pad1)") (class "Default")
      (node (ref "R55") (pin "1") (pinfunction "1_1") (pintype "passive"))
      (node (ref "R56") (pin "2") (pinfunction "2_2") (pintype "passive"))
    )
    (net (code "72") (name "Net-(R56-Pad1)") (class "Default")
      (node (ref "R56") (pin "1") (pinfunction "1_1") (pintype "passive"))
      (node (ref "R57") (pin "2") (pinfunction "2_2") (pintype "passive"))
    )
    (net (code "73") (name "Net-(R57-Pad1)") (class "Default")
      (node (ref "R57") (pin "1") (pinfunction "1_1") (pintype "passive"))
      (node (ref "R58") (pin "2") (pinfunction "2_2") (pintype "passive"))
    )
    (net (code "74") (name "Net-(R58-Pad1)") (class "Default")
      (node (ref "R58") (pin "1") (pinfunction "1_1") (pintype "passive"))
      (node (ref "R59") (pin "2") (pinfunction "2_2") (pintype "passive"))
    )
    (net (code "75") (name "Net-(R59-Pad1)") (class "Default")
      (node (ref "R59") (pin "1") (pinfunction "1_1") (pintype "passive"))
      (node (ref "R60") (pin "2") (pinfunction "2_2") (pintype "passive"))
    )
    (net (code "76") (name "Net-(R60-Pad1)") (class "Default")
      (node (ref "R60") (pin "1") (pinfunction "1_1") (pintype "passive"))
      (node (ref "R61") (pin "2") (pinfunction "2_2") (pintype "passive"))
    )
    (net (code "77") (name "Net-(U6-OSCI)") (class "Default")
      (node (ref "U6") (pin "20") (pinfunction "OSCI_20") (pintype "input"))
      (node (ref "X1") (pin "1") (pinfunction "1_1") (pintype "passive"))
    )
    (net (code "78") (name "Net-(U6-OSCO)") (class "Default")
      (node (ref "U6") (pin "21") (pinfunction "OSCO_21") (pintype "output"))
      (node (ref "X1") (pin "2") (pinfunction "2_2") (pintype "passive"))
    )
  )
)
